# EncoderPCB_V1_2.net
KiCad netlist of a schematic drawn in EAGLE
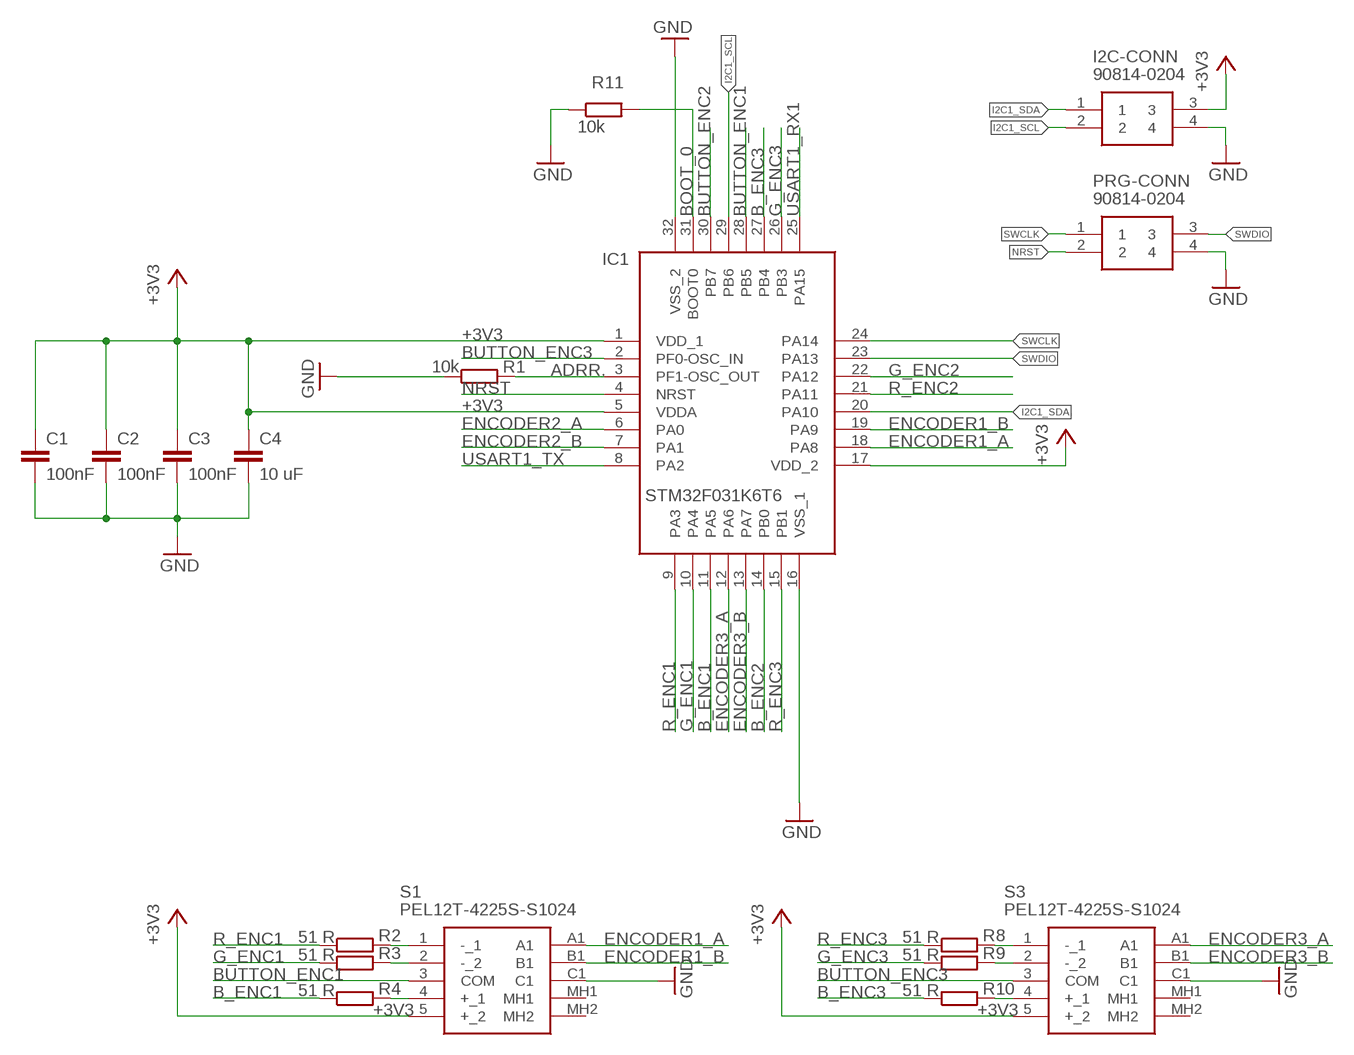
[diagram p0: schematic, sheet 1]

(export (version "E")
  (design (tool "Eeschema 10.0.6"))
  (components
    (comp (ref "C1")
      (value "100nF")
      (footprint "eagle-import:C0603")
      (libsource (lib "eagle-import") (part "CAPACITOR{dblquote}"))
    )
    (comp (ref "C2")
      (value "100nF")
      (footprint "eagle-import:C0603")
      (libsource (lib "eagle-import") (part "CAPACITOR{dblquote}"))
    )
    (comp (ref "C3")
      (value "100nF")
      (footprint "eagle-import:C0603")
      (libsource (lib "eagle-import") (part "CAPACITOR{dblquote}"))
    )
    (comp (ref "C4")
      (value "10 uF")
      (footprint "eagle-import:C1206")
      (libsource (lib "eagle-import") (part "CAPACITOR_1206"))
    )
    (comp (ref "I2C-CONN")
      (value "90814-0204")
      (footprint "eagle-import:MOLEX_90814-0204")
      (fields (field (name "MOUSER_PART_NUMBER") "538-90814-0204"))
      (libsource (lib "eagle-import") (part "90814-0204"))
    )
    (comp (ref "IC1")
      (value "STM32F031K6T6")
      (footprint "eagle-import:QFP80P900X900X160-32N")
      (fields (field (name "MOUSER_PART_NUMBER") "511-STM32F031K6T6"))
      (libsource (lib "eagle-import") (part "STM32F031K6T6"))
    )
    (comp (ref "PRG-CONN")
      (value "90814-0204")
      (footprint "eagle-import:MOLEX_90814-0204")
      (fields (field (name "MOUSER_PART_NUMBER") "538-90814-0204"))
      (libsource (lib "eagle-import") (part "90814-0204"))
    )
    (comp (ref "R1")
      (value "10k")
      (footprint "eagle-import:R0603")
      (libsource (lib "eagle-import") (part "RESISTOR_0603"))
    )
    (comp (ref "R2")
      (value "51 R")
      (footprint "eagle-import:R0603")
      (libsource (lib "eagle-import") (part "RESISTOR_0603"))
    )
    (comp (ref "R3")
      (value "51 R")
      (footprint "eagle-import:R0603")
      (libsource (lib "eagle-import") (part "RESISTOR_0603"))
    )
    (comp (ref "R4")
      (value "51 R")
      (footprint "eagle-import:R0603")
      (libsource (lib "eagle-import") (part "RESISTOR_0603"))
    )
    (comp (ref "R8")
      (value "51 R")
      (footprint "eagle-import:R0603")
      (libsource (lib "eagle-import") (part "RESISTOR_0603"))
    )
    (comp (ref "R9")
      (value "51 R")
      (footprint "eagle-import:R0603")
      (libsource (lib "eagle-import") (part "RESISTOR_0603"))
    )
    (comp (ref "R10")
      (value "51 R")
      (footprint "eagle-import:R0603")
      (libsource (lib "eagle-import") (part "RESISTOR_0603"))
    )
    (comp (ref "R11")
      (value "10k")
      (footprint "eagle-import:R0603")
      (libsource (lib "eagle-import") (part "RESISTOR_0603"))
    )
    (comp (ref "S1")
      (value "PEL12T-4225S-S1024")
      (footprint "eagle-import:PEL12T4225SS1024")
      (fields (field (name "MOUSER_PART_NUMBER") "652-PEL12T4225SS1024"))
      (libsource (lib "eagle-import") (part "PEL12T-4225S-S1024"))
    )
    (comp (ref "S3")
      (value "PEL12T-4225S-S1024")
      (footprint "eagle-import:PEL12T4225SS1024")
      (fields (field (name "MOUSER_PART_NUMBER") "652-PEL12T4225SS1024"))
      (libsource (lib "eagle-import") (part "PEL12T-4225S-S1024"))
    )
  )
  (nets
    (net (code "1") (name "+3V3") (class "Default")
      (node (ref "C1") (pin "1") (pinfunction "1_1") (pintype "passive"))
      (node (ref "C2") (pin "1") (pinfunction "1_1") (pintype "passive"))
      (node (ref "C3") (pin "1") (pinfunction "1_1") (pintype "passive"))
      (node (ref "C4") (pin "1") (pinfunction "1_1") (pintype "passive"))
      (node (ref "I2C-CONN") (pin "3") (pinfunction "3_3") (pintype "bidirectional"))
      (node (ref "IC1") (pin "1") (pinfunction "VDD_1_1") (pintype "bidirectional"))
      (node (ref "IC1") (pin "17") (pinfunction "VDD_2_17") (pintype "bidirectional"))
      (node (ref "IC1") (pin "5") (pinfunction "VDDA_5") (pintype "bidirectional"))
      (node (ref "S1") (pin "5") (pinfunction "+_2_5") (pintype "bidirectional"))
      (node (ref "S3") (pin "5") (pinfunction "+_2_5") (pintype "bidirectional"))
    )
    (net (code "2") (name "/ADRR.") (class "Default")
      (node (ref "IC1") (pin "3") (pinfunction "PF1-OSC_OUT_3") (pintype "bidirectional"))
      (node (ref "R1") (pin "2") (pinfunction "2_2") (pintype "passive"))
    )
    (net (code "3") (name "/BOOT_0") (class "Default")
      (node (ref "IC1") (pin "31") (pinfunction "BOOT0_31") (pintype "bidirectional"))
      (node (ref "R11") (pin "2") (pinfunction "2_2") (pintype "passive"))
    )
    (net (code "4") (name "/BUTTON_ENC1") (class "Default")
      (node (ref "IC1") (pin "28") (pinfunction "PB5_28") (pintype "bidirectional"))
      (node (ref "S1") (pin "3") (pinfunction "COM_3") (pintype "bidirectional"))
    )
    (net (code "5") (name "/BUTTON_ENC2") (class "Default")
      (node (ref "IC1") (pin "30") (pinfunction "PB7_30") (pintype "bidirectional"))
    )
    (net (code "6") (name "/BUTTON_ENC3") (class "Default")
      (node (ref "IC1") (pin "2") (pinfunction "PF0-OSC_IN_2") (pintype "bidirectional"))
      (node (ref "S3") (pin "3") (pinfunction "COM_3") (pintype "bidirectional"))
    )
    (net (code "7") (name "/B_ENC1") (class "Default")
      (node (ref "IC1") (pin "11") (pinfunction "PA5_11") (pintype "bidirectional"))
      (node (ref "R4") (pin "1") (pinfunction "1_1") (pintype "passive"))
    )
    (net (code "8") (name "/B_ENC2") (class "Default")
      (node (ref "IC1") (pin "14") (pinfunction "PB0_14") (pintype "bidirectional"))
    )
    (net (code "9") (name "/B_ENC3") (class "Default")
      (node (ref "IC1") (pin "27") (pinfunction "PB4_27") (pintype "bidirectional"))
      (node (ref "R10") (pin "1") (pinfunction "1_1") (pintype "passive"))
    )
    (net (code "10") (name "/ENCODER1_A") (class "Default")
      (node (ref "IC1") (pin "18") (pinfunction "PA8_18") (pintype "bidirectional"))
      (node (ref "S1") (pin "A1") (pinfunction "A1_A1") (pintype "bidirectional"))
    )
    (net (code "11") (name "/ENCODER1_B") (class "Default")
      (node (ref "IC1") (pin "19") (pinfunction "PA9_19") (pintype "bidirectional"))
      (node (ref "S1") (pin "B1") (pinfunction "B1_B1") (pintype "bidirectional"))
    )
    (net (code "12") (name "/ENCODER2_A") (class "Default")
      (node (ref "IC1") (pin "6") (pinfunction "PA0_6") (pintype "bidirectional"))
    )
    (net (code "13") (name "/ENCODER2_B") (class "Default")
      (node (ref "IC1") (pin "7") (pinfunction "PA1_7") (pintype "bidirectional"))
    )
    (net (code "14") (name "/ENCODER3_A") (class "Default")
      (node (ref "IC1") (pin "12") (pinfunction "PA6_12") (pintype "bidirectional"))
      (node (ref "S3") (pin "A1") (pinfunction "A1_A1") (pintype "bidirectional"))
    )
    (net (code "15") (name "/ENCODER3_B") (class "Default")
      (node (ref "IC1") (pin "13") (pinfunction "PA7_13") (pintype "bidirectional"))
      (node (ref "S3") (pin "B1") (pinfunction "B1_B1") (pintype "bidirectional"))
    )
    (net (code "16") (name "/G_ENC1") (class "Default")
      (node (ref "IC1") (pin "10") (pinfunction "PA4_10") (pintype "bidirectional"))
      (node (ref "R3") (pin "1") (pinfunction "1_1") (pintype "passive"))
    )
    (net (code "17") (name "/G_ENC2") (class "Default")
      (node (ref "IC1") (pin "22") (pinfunction "PA12_22") (pintype "bidirectional"))
    )
    (net (code "18") (name "/G_ENC3") (class "Default")
      (node (ref "IC1") (pin "26") (pinfunction "PB3_26") (pintype "bidirectional"))
      (node (ref "R9") (pin "1") (pinfunction "1_1") (pintype "passive"))
    )
    (net (code "19") (name "/R_ENC1") (class "Default")
      (node (ref "IC1") (pin "9") (pinfunction "PA3_9") (pintype "bidirectional"))
      (node (ref "R2") (pin "1") (pinfunction "1_1") (pintype "passive"))
    )
    (net (code "20") (name "/R_ENC2") (class "Default")
      (node (ref "IC1") (pin "21") (pinfunction "PA11_21") (pintype "bidirectional"))
    )
    (net (code "21") (name "/R_ENC3") (class "Default")
      (node (ref "IC1") (pin "15") (pinfunction "PB1_15") (pintype "bidirectional"))
      (node (ref "R8") (pin "1") (pinfunction "1_1") (pintype "passive"))
    )
    (net (code "22") (name "/USART1_RX1") (class "Default")
      (node (ref "IC1") (pin "25") (pinfunction "PA15_25") (pintype "bidirectional"))
    )
    (net (code "23") (name "/USART1_TX") (class "Default")
      (node (ref "IC1") (pin "8") (pinfunction "PA2_8") (pintype "bidirectional"))
    )
    (net (code "24") (name "GND") (class "Default")
      (node (ref "C1") (pin "2") (pinfunction "2_2") (pintype "passive"))
      (node (ref "C2") (pin "2") (pinfunction "2_2") (pintype "passive"))
      (node (ref "C3") (pin "2") (pinfunction "2_2") (pintype "passive"))
      (node (ref "C4") (pin "2") (pinfunction "2_2") (pintype "passive"))
      (node (ref "I2C-CONN") (pin "4") (pinfunction "4_4") (pintype "bidirectional"))
      (node (ref "IC1") (pin "16") (pinfunction "VSS_1_16") (pintype "bidirectional"))
      (node (ref "IC1") (pin "32") (pinfunction "VSS_2_32") (pintype "bidirectional"))
      (node (ref "PRG-CONN") (pin "4") (pinfunction "4_4") (pintype "bidirectional"))
      (node (ref "R1") (pin "1") (pinfunction "1_1") (pintype "passive"))
      (node (ref "R11") (pin "1") (pinfunction "1_1") (pintype "passive"))
      (node (ref "S1") (pin "C1") (pinfunction "C1_C1") (pintype "bidirectional"))
      (node (ref "S3") (pin "C1") (pinfunction "C1_C1") (pintype "bidirectional"))
    )
    (net (code "25") (name "I2C1_SCL") (class "Default")
      (node (ref "I2C-CONN") (pin "2") (pinfunction "2_2") (pintype "bidirectional"))
      (node (ref "IC1") (pin "29") (pinfunction "PB6_29") (pintype "bidirectional"))
    )
    (net (code "26") (name "I2C1_SDA") (class "Default")
      (node (ref "I2C-CONN") (pin "1") (pinfunction "1_1") (pintype "bidirectional"))
      (node (ref "IC1") (pin "20") (pinfunction "PA10_20") (pintype "bidirectional"))
    )
    (net (code "27") (name "NRST") (class "Default")
      (node (ref "IC1") (pin "4") (pinfunction "NRST_4") (pintype "bidirectional"))
      (node (ref "PRG-CONN") (pin "2") (pinfunction "2_2") (pintype "bidirectional"))
    )
    (net (code "28") (name "Net-(S1-+_1)") (class "Default")
      (node (ref "R4") (pin "2") (pinfunction "2_2") (pintype "passive"))
      (node (ref "S1") (pin "4") (pinfunction "+_1_4") (pintype "bidirectional"))
    )
    (net (code "29") (name "Net-(S1--_1)") (class "Default")
      (node (ref "R2") (pin "2") (pinfunction "2_2") (pintype "passive"))
      (node (ref "S1") (pin "1") (pinfunction "-_1_1") (pintype "bidirectional"))
    )
    (net (code "30") (name "Net-(S1--_2)") (class "Default")
      (node (ref "R3") (pin "2") (pinfunction "2_2") (pintype "passive"))
      (node (ref "S1") (pin "2") (pinfunction "-_2_2") (pintype "bidirectional"))
    )
    (net (code "31") (name "Net-(S3-+_1)") (class "Default")
      (node (ref "R10") (pin "2") (pinfunction "2_2") (pintype "passive"))
      (node (ref "S3") (pin "4") (pinfunction "+_1_4") (pintype "bidirectional"))
    )
    (net (code "32") (name "Net-(S3--_1)") (class "Default")
      (node (ref "R8") (pin "2") (pinfunction "2_2") (pintype "passive"))
      (node (ref "S3") (pin "1") (pinfunction "-_1_1") (pintype "bidirectional"))
    )
    (net (code "33") (name "Net-(S3--_2)") (class "Default")
      (node (ref "R9") (pin "2") (pinfunction "2_2") (pintype "passive"))
      (node (ref "S3") (pin "2") (pinfunction "-_2_2") (pintype "bidirectional"))
    )
    (net (code "34") (name "SWCLK") (class "Default")
      (node (ref "IC1") (pin "24") (pinfunction "PA14_24") (pintype "bidirectional"))
      (node (ref "PRG-CONN") (pin "1") (pinfunction "1_1") (pintype "bidirectional"))
    )
    (net (code "35") (name "SWDIO") (class "Default")
      (node (ref "IC1") (pin "23") (pinfunction "PA13_23") (pintype "bidirectional"))
      (node (ref "PRG-CONN") (pin "3") (pinfunction "3_3") (pintype "bidirectional"))
    )
    (net (code "36") (name "unconnected-(S1-PadMH1)") (class "Default")
      (node (ref "S1") (pin "MH1") (pinfunction "MH1_MH1") (pintype "bidirectional"))
    )
    (net (code "37") (name "unconnected-(S1-PadMH2)") (class "Default")
      (node (ref "S1") (pin "MH2") (pinfunction "MH2_MH2") (pintype "bidirectional"))
    )
    (net (code "38") (name "unconnected-(S3-PadMH1)") (class "Default")
      (node (ref "S3") (pin "MH1") (pinfunction "MH1_MH1") (pintype "bidirectional"))
    )
    (net (code "39") (name "unconnected-(S3-PadMH2)") (class "Default")
      (node (ref "S3") (pin "MH2") (pinfunction "MH2_MH2") (pintype "bidirectional"))
    )
  )
)
